# 4_digit_display.net
KiCad netlist of a schematic drawn in EAGLE
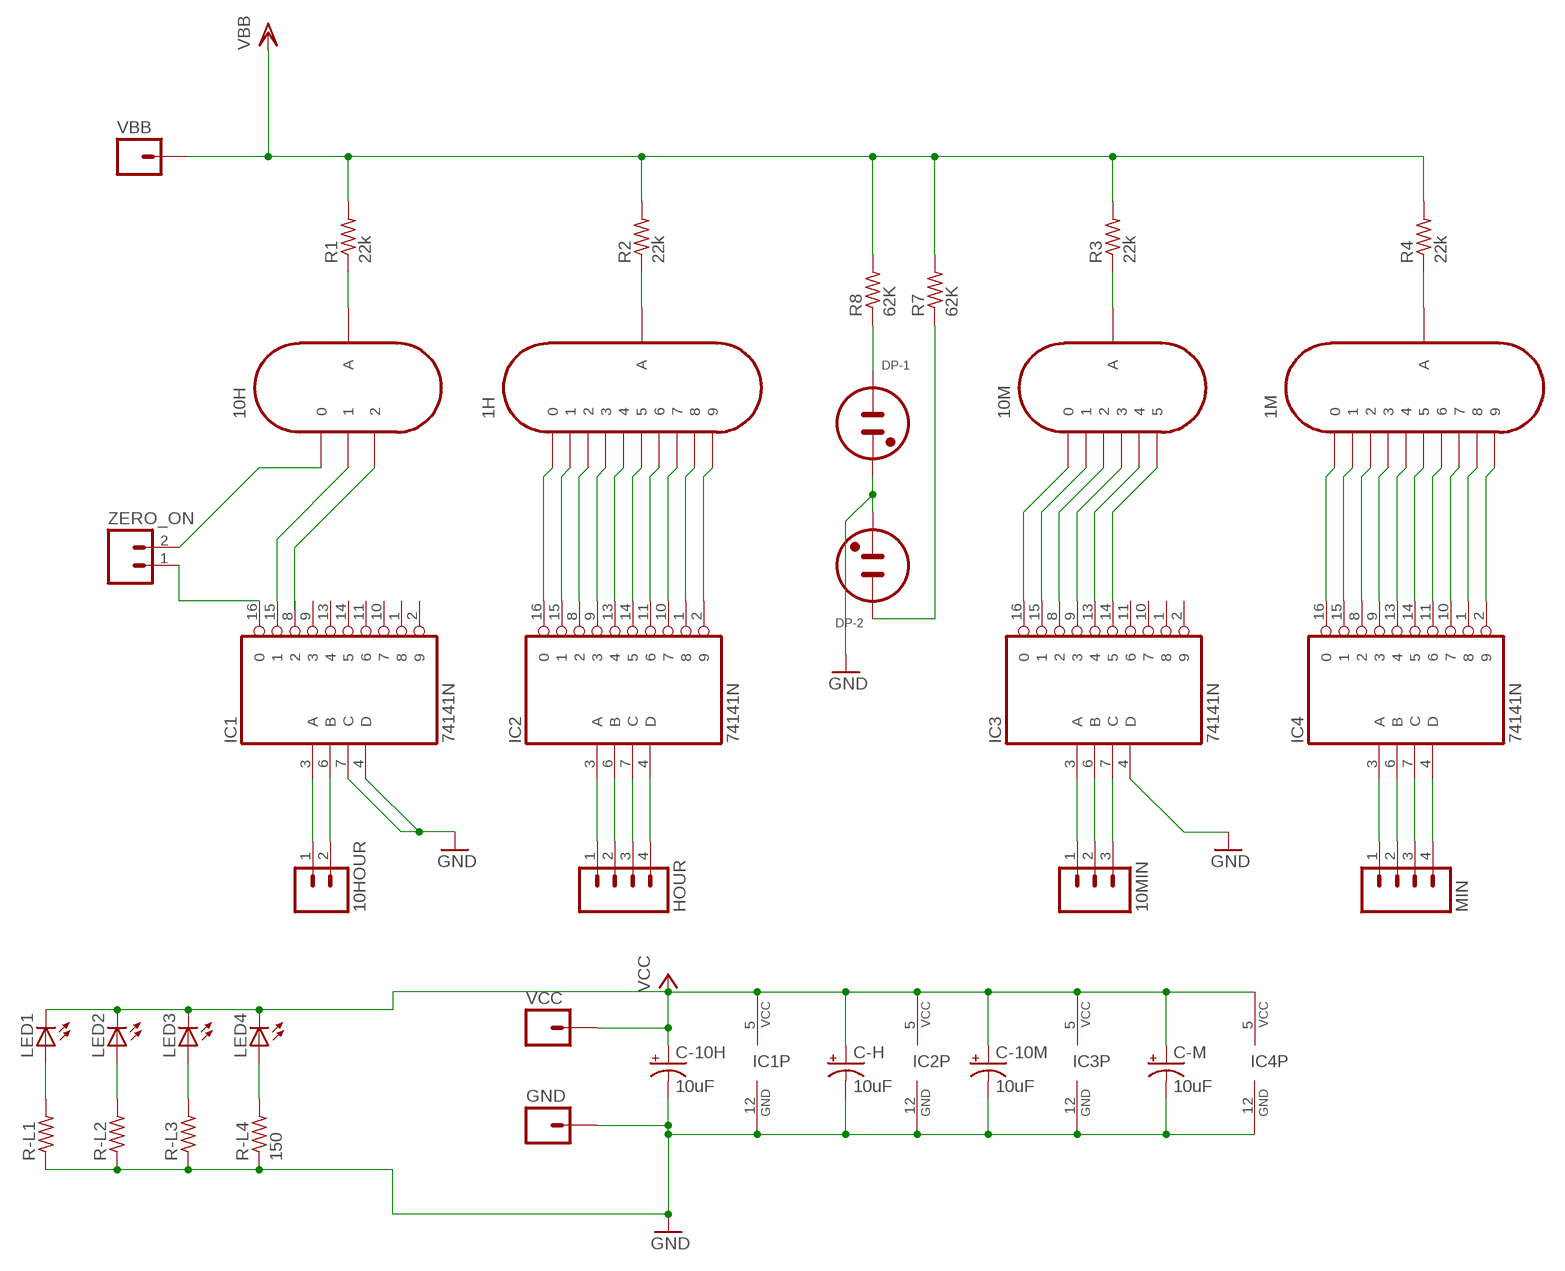
[diagram p0: schematic, sheet 1]

(export (version "E")
  (design (tool "Eeschema 10.0.6"))
  (components
    (comp (ref "1H")
      (value "IN-12A-NO_DP")
      (footprint "eagle-import:IN-12_NO-DP")
      (libsource (lib "eagle-import") (part "IN-12A-NO_DP"))
    )
    (comp (ref "1M")
      (value "IN-12A-NO_DP")
      (footprint "eagle-import:IN-12_NO-DP")
      (libsource (lib "eagle-import") (part "IN-12A-NO_DP"))
    )
    (comp (ref "10H")
      (value "IN-12_2DIGIT")
      (footprint "eagle-import:IN-12_2DIGIT")
      (libsource (lib "eagle-import") (part "IN-12_2DIGIT"))
    )
    (comp (ref "10HOUR")
      (value "M02PTH")
      (footprint "eagle-import:1X02")
      (libsource (lib "eagle-import") (part "M02PTH"))
    )
    (comp (ref "10M")
      (value "IN-12_6DIGIT")
      (footprint "eagle-import:IN-12_6DIGIT")
      (libsource (lib "eagle-import") (part "IN-12_6DIGIT"))
    )
    (comp (ref "10MIN")
      (value "M03PTH")
      (footprint "eagle-import:1X03")
      (libsource (lib "eagle-import") (part "M03PTH"))
    )
    (comp (ref "C-10H")
      (value "10uF")
      (footprint "eagle-import:B_3528-21R")
      (libsource (lib "eagle-import") (part "CAPACITOR_POLB/3528-21R"))
    )
    (comp (ref "C-10M")
      (value "10uF")
      (footprint "eagle-import:B_3528-21R")
      (libsource (lib "eagle-import") (part "CAPACITOR_POLB/3528-21R"))
    )
    (comp (ref "C-H")
      (value "10uF")
      (footprint "eagle-import:B_3528-21R")
      (libsource (lib "eagle-import") (part "CAPACITOR_POLB/3528-21R"))
    )
    (comp (ref "C-M")
      (value "10uF")
      (footprint "eagle-import:B_3528-21R")
      (libsource (lib "eagle-import") (part "CAPACITOR_POLB/3528-21R"))
    )
    (comp (ref "DP-1")
      (value "INS-1")
      (footprint "eagle-import:INS-1")
      (libsource (lib "eagle-import") (part "INS-1"))
    )
    (comp (ref "DP-2")
      (value "INS-1")
      (footprint "eagle-import:INS-1")
      (libsource (lib "eagle-import") (part "INS-1"))
    )
    (comp (ref "GND")
      (value "M01PTH")
      (footprint "eagle-import:1X01")
      (libsource (lib "eagle-import") (part "M01PTH"))
    )
    (comp (ref "HOUR")
      (value "M04PTH")
      (footprint "eagle-import:1X04")
      (libsource (lib "eagle-import") (part "M04PTH"))
    )
    (comp (ref "IC1")
      (value "74141N")
      (footprint "eagle-import:DIL16")
      (libsource (lib "eagle-import") (part "74141N"))
    )
    (comp (ref "IC2")
      (value "74141N")
      (footprint "eagle-import:DIL16")
      (libsource (lib "eagle-import") (part "74141N"))
    )
    (comp (ref "IC3")
      (value "74141N")
      (footprint "eagle-import:DIL16")
      (libsource (lib "eagle-import") (part "74141N"))
    )
    (comp (ref "IC4")
      (value "74141N")
      (footprint "eagle-import:DIL16")
      (libsource (lib "eagle-import") (part "74141N"))
    )
    (comp (ref "LED1")
      (value "LED1210")
      (footprint "eagle-import:LED1210")
      (libsource (lib "eagle-import") (part "LED1210"))
    )
    (comp (ref "LED2")
      (value "LED1210")
      (footprint "eagle-import:LED1210")
      (libsource (lib "eagle-import") (part "LED1210"))
    )
    (comp (ref "LED3")
      (value "LED1210")
      (footprint "eagle-import:LED1210")
      (libsource (lib "eagle-import") (part "LED1210"))
    )
    (comp (ref "LED4")
      (value "LED1210")
      (footprint "eagle-import:LED1210")
      (libsource (lib "eagle-import") (part "LED1210"))
    )
    (comp (ref "MIN")
      (value "M04PTH")
      (footprint "eagle-import:1X04")
      (libsource (lib "eagle-import") (part "M04PTH"))
    )
    (comp (ref "R-L1")
      (value "RESISTORR1206")
      (footprint "eagle-import:R1206")
      (libsource (lib "eagle-import") (part "RESISTORR1206"))
    )
    (comp (ref "R-L2")
      (value "RESISTORR1206")
      (footprint "eagle-import:R1206")
      (libsource (lib "eagle-import") (part "RESISTORR1206"))
    )
    (comp (ref "R-L3")
      (value "RESISTORR1206")
      (footprint "eagle-import:R1206")
      (libsource (lib "eagle-import") (part "RESISTORR1206"))
    )
    (comp (ref "R-L4")
      (value "150")
      (footprint "eagle-import:R1206")
      (libsource (lib "eagle-import") (part "RESISTORR1206"))
    )
    (comp (ref "R1")
      (value "22k")
      (footprint "eagle-import:0207_10")
      (libsource (lib "eagle-import") (part "RESISTOR0207/10"))
    )
    (comp (ref "R2")
      (value "22k")
      (footprint "eagle-import:0207_10")
      (libsource (lib "eagle-import") (part "RESISTOR0207/10"))
    )
    (comp (ref "R3")
      (value "22k")
      (footprint "eagle-import:0207_10")
      (libsource (lib "eagle-import") (part "RESISTOR0207/10"))
    )
    (comp (ref "R4")
      (value "22k")
      (footprint "eagle-import:0207_10")
      (libsource (lib "eagle-import") (part "RESISTOR0207/10"))
    )
    (comp (ref "R7")
      (value "62K")
      (footprint "eagle-import:0207_10")
      (libsource (lib "eagle-import") (part "RESISTOR0207/10"))
    )
    (comp (ref "R8")
      (value "62K")
      (footprint "eagle-import:0207_10")
      (libsource (lib "eagle-import") (part "RESISTOR0207/10"))
    )
    (comp (ref "VBB")
      (value "M01PTH")
      (footprint "eagle-import:1X01")
      (libsource (lib "eagle-import") (part "M01PTH"))
    )
    (comp (ref "VCC")
      (value "M01PTH")
      (footprint "eagle-import:1X01")
      (libsource (lib "eagle-import") (part "M01PTH"))
    )
    (comp (ref "ZERO_ON")
      (value "M02PTH")
      (footprint "eagle-import:1X02")
      (libsource (lib "eagle-import") (part "M02PTH"))
    )
  )
  (nets
    (net (code "1") (name "GND") (class "Default")
      (node (ref "C-10H") (pin "-") (pinfunction "-_-") (pintype "passive"))
      (node (ref "C-10M") (pin "-") (pinfunction "-_-") (pintype "passive"))
      (node (ref "C-H") (pin "-") (pinfunction "-_-") (pintype "passive"))
      (node (ref "C-M") (pin "-") (pinfunction "-_-") (pintype "passive"))
      (node (ref "DP-1") (pin "K") (pinfunction "K_K") (pintype "passive"))
      (node (ref "DP-2") (pin "K") (pinfunction "K_K") (pintype "passive"))
      (node (ref "GND") (pin "1") (pinfunction "1_1") (pintype "passive"))
      (node (ref "IC1") (pin "12") (pinfunction "GND_12") (pintype "power_in"))
      (node (ref "IC1") (pin "4") (pinfunction "D_4") (pintype "input"))
      (node (ref "IC1") (pin "7") (pinfunction "C_7") (pintype "input"))
      (node (ref "IC2") (pin "12") (pinfunction "GND_12") (pintype "power_in"))
      (node (ref "IC3") (pin "12") (pinfunction "GND_12") (pintype "power_in"))
      (node (ref "IC3") (pin "4") (pinfunction "D_4") (pintype "input"))
      (node (ref "IC4") (pin "12") (pinfunction "GND_12") (pintype "power_in"))
      (node (ref "R-L1") (pin "1") (pinfunction "1_1") (pintype "passive"))
      (node (ref "R-L2") (pin "1") (pinfunction "1_1") (pintype "passive"))
      (node (ref "R-L3") (pin "1") (pinfunction "1_1") (pintype "passive"))
      (node (ref "R-L4") (pin "1") (pinfunction "1_1") (pintype "passive"))
    )
    (net (code "2") (name "Net-(1H-PadA)") (class "Default")
      (node (ref "1H") (pin "A") (pinfunction "A_A") (pintype "bidirectional"))
      (node (ref "R2") (pin "1") (pinfunction "1_1") (pintype "passive"))
    )
    (net (code "3") (name "Net-(1M-PadA)") (class "Default")
      (node (ref "1M") (pin "A") (pinfunction "A_A") (pintype "bidirectional"))
      (node (ref "R4") (pin "1") (pinfunction "1_1") (pintype "passive"))
    )
    (net (code "4") (name "Net-(10H-Pad0)") (class "Default")
      (node (ref "10H") (pin "0") (pinfunction "0_0") (pintype "bidirectional"))
      (node (ref "ZERO_ON") (pin "2") (pinfunction "2_2") (pintype "passive"))
    )
    (net (code "5") (name "Net-(10H-PadA)") (class "Default")
      (node (ref "10H") (pin "A") (pinfunction "A_A") (pintype "bidirectional"))
      (node (ref "R1") (pin "1") (pinfunction "1_1") (pintype "passive"))
    )
    (net (code "6") (name "Net-(10M-PadA)") (class "Default")
      (node (ref "10M") (pin "A") (pinfunction "A_A") (pintype "bidirectional"))
      (node (ref "R3") (pin "1") (pinfunction "1_1") (pintype "passive"))
    )
    (net (code "7") (name "Net-(DP-1-PadA)") (class "Default")
      (node (ref "DP-1") (pin "A") (pinfunction "A_A") (pintype "passive"))
      (node (ref "R8") (pin "1") (pinfunction "1_1") (pintype "passive"))
    )
    (net (code "8") (name "Net-(DP-2-PadA)") (class "Default")
      (node (ref "DP-2") (pin "A") (pinfunction "A_A") (pintype "passive"))
      (node (ref "R7") (pin "1") (pinfunction "1_1") (pintype "passive"))
    )
    (net (code "9") (name "Net-(IC1A-0)") (class "Default")
      (node (ref "IC1") (pin "16") (pinfunction "0_16") (pintype "open_collector"))
      (node (ref "ZERO_ON") (pin "1") (pinfunction "1_1") (pintype "passive"))
    )
    (net (code "10") (name "Net-(IC1A-1)") (class "Default")
      (node (ref "10H") (pin "1") (pinfunction "1_1") (pintype "bidirectional"))
      (node (ref "IC1") (pin "15") (pinfunction "1_15") (pintype "open_collector"))
    )
    (net (code "11") (name "Net-(IC1A-A)") (class "Default")
      (node (ref "10HOUR") (pin "1") (pinfunction "1_1") (pintype "passive"))
      (node (ref "IC1") (pin "3") (pinfunction "A_3") (pintype "input"))
    )
    (net (code "12") (name "Net-(IC1A-B)") (class "Default")
      (node (ref "10HOUR") (pin "2") (pinfunction "2_2") (pintype "passive"))
      (node (ref "IC1") (pin "6") (pinfunction "B_6") (pintype "input"))
    )
    (net (code "13") (name "Net-(IC2A-0)") (class "Default")
      (node (ref "1H") (pin "0") (pinfunction "0_0") (pintype "bidirectional"))
      (node (ref "IC2") (pin "16") (pinfunction "0_16") (pintype "open_collector"))
    )
    (net (code "14") (name "Net-(IC2A-1)") (class "Default")
      (node (ref "1H") (pin "1") (pinfunction "1_1") (pintype "bidirectional"))
      (node (ref "IC2") (pin "15") (pinfunction "1_15") (pintype "open_collector"))
    )
    (net (code "15") (name "Net-(IC2A-2)") (class "Default")
      (node (ref "1H") (pin "2") (pinfunction "2_2") (pintype "bidirectional"))
      (node (ref "IC2") (pin "8") (pinfunction "2_8") (pintype "open_collector"))
    )
    (net (code "16") (name "Net-(IC2A-3)") (class "Default")
      (node (ref "1H") (pin "3") (pinfunction "3_3") (pintype "bidirectional"))
      (node (ref "IC2") (pin "9") (pinfunction "3_9") (pintype "open_collector"))
    )
    (net (code "17") (name "Net-(IC2A-4)") (class "Default")
      (node (ref "1H") (pin "4") (pinfunction "4_4") (pintype "bidirectional"))
      (node (ref "IC2") (pin "13") (pinfunction "4_13") (pintype "open_collector"))
    )
    (net (code "18") (name "Net-(IC2A-5)") (class "Default")
      (node (ref "1H") (pin "5") (pinfunction "5_5") (pintype "bidirectional"))
      (node (ref "IC2") (pin "14") (pinfunction "5_14") (pintype "open_collector"))
    )
    (net (code "19") (name "Net-(IC2A-6)") (class "Default")
      (node (ref "1H") (pin "6") (pinfunction "6_6") (pintype "bidirectional"))
      (node (ref "IC2") (pin "11") (pinfunction "6_11") (pintype "open_collector"))
    )
    (net (code "20") (name "Net-(IC2A-7)") (class "Default")
      (node (ref "1H") (pin "7") (pinfunction "7_7") (pintype "bidirectional"))
      (node (ref "IC2") (pin "10") (pinfunction "7_10") (pintype "open_collector"))
    )
    (net (code "21") (name "Net-(IC2A-8)") (class "Default")
      (node (ref "1H") (pin "8") (pinfunction "8_8") (pintype "bidirectional"))
      (node (ref "IC2") (pin "1") (pinfunction "8_1") (pintype "open_collector"))
    )
    (net (code "22") (name "Net-(IC2A-9)") (class "Default")
      (node (ref "1H") (pin "9") (pinfunction "9_9") (pintype "bidirectional"))
      (node (ref "IC2") (pin "2") (pinfunction "9_2") (pintype "open_collector"))
    )
    (net (code "23") (name "Net-(IC2A-A)") (class "Default")
      (node (ref "HOUR") (pin "1") (pinfunction "1_1") (pintype "passive"))
      (node (ref "IC2") (pin "3") (pinfunction "A_3") (pintype "input"))
    )
    (net (code "24") (name "Net-(IC2A-B)") (class "Default")
      (node (ref "HOUR") (pin "2") (pinfunction "2_2") (pintype "passive"))
      (node (ref "IC2") (pin "6") (pinfunction "B_6") (pintype "input"))
    )
    (net (code "25") (name "Net-(IC2A-C)") (class "Default")
      (node (ref "HOUR") (pin "3") (pinfunction "3_3") (pintype "passive"))
      (node (ref "IC2") (pin "7") (pinfunction "C_7") (pintype "input"))
    )
    (net (code "26") (name "Net-(IC2A-D)") (class "Default")
      (node (ref "HOUR") (pin "4") (pinfunction "4_4") (pintype "passive"))
      (node (ref "IC2") (pin "4") (pinfunction "D_4") (pintype "input"))
    )
    (net (code "27") (name "Net-(IC3A-0)") (class "Default")
      (node (ref "10M") (pin "0") (pinfunction "0_0") (pintype "bidirectional"))
      (node (ref "IC3") (pin "16") (pinfunction "0_16") (pintype "open_collector"))
    )
    (net (code "28") (name "Net-(IC3A-1)") (class "Default")
      (node (ref "10M") (pin "1") (pinfunction "1_1") (pintype "bidirectional"))
      (node (ref "IC3") (pin "15") (pinfunction "1_15") (pintype "open_collector"))
    )
    (net (code "29") (name "Net-(IC3A-2)") (class "Default")
      (node (ref "10M") (pin "2") (pinfunction "2_2") (pintype "bidirectional"))
      (node (ref "IC3") (pin "8") (pinfunction "2_8") (pintype "open_collector"))
    )
    (net (code "30") (name "Net-(IC3A-3)") (class "Default")
      (node (ref "10M") (pin "3") (pinfunction "3_3") (pintype "bidirectional"))
      (node (ref "IC3") (pin "9") (pinfunction "3_9") (pintype "open_collector"))
    )
    (net (code "31") (name "Net-(IC3A-4)") (class "Default")
      (node (ref "10M") (pin "4") (pinfunction "4_4") (pintype "bidirectional"))
      (node (ref "IC3") (pin "13") (pinfunction "4_13") (pintype "open_collector"))
    )
    (net (code "32") (name "Net-(IC3A-5)") (class "Default")
      (node (ref "10M") (pin "5") (pinfunction "5_5") (pintype "bidirectional"))
      (node (ref "IC3") (pin "14") (pinfunction "5_14") (pintype "open_collector"))
    )
    (net (code "33") (name "Net-(IC3A-A)") (class "Default")
      (node (ref "10MIN") (pin "1") (pinfunction "1_1") (pintype "passive"))
      (node (ref "IC3") (pin "3") (pinfunction "A_3") (pintype "input"))
    )
    (net (code "34") (name "Net-(IC3A-B)") (class "Default")
      (node (ref "10MIN") (pin "2") (pinfunction "2_2") (pintype "passive"))
      (node (ref "IC3") (pin "6") (pinfunction "B_6") (pintype "input"))
    )
    (net (code "35") (name "Net-(IC3A-C)") (class "Default")
      (node (ref "10MIN") (pin "3") (pinfunction "3_3") (pintype "passive"))
      (node (ref "IC3") (pin "7") (pinfunction "C_7") (pintype "input"))
    )
    (net (code "36") (name "Net-(IC4A-0)") (class "Default")
      (node (ref "1M") (pin "0") (pinfunction "0_0") (pintype "bidirectional"))
      (node (ref "IC4") (pin "16") (pinfunction "0_16") (pintype "open_collector"))
    )
    (net (code "37") (name "Net-(IC4A-1)") (class "Default")
      (node (ref "1M") (pin "1") (pinfunction "1_1") (pintype "bidirectional"))
      (node (ref "IC4") (pin "15") (pinfunction "1_15") (pintype "open_collector"))
    )
    (net (code "38") (name "Net-(IC4A-2)") (class "Default")
      (node (ref "1M") (pin "2") (pinfunction "2_2") (pintype "bidirectional"))
      (node (ref "IC4") (pin "8") (pinfunction "2_8") (pintype "open_collector"))
    )
    (net (code "39") (name "Net-(IC4A-3)") (class "Default")
      (node (ref "1M") (pin "3") (pinfunction "3_3") (pintype "bidirectional"))
      (node (ref "IC4") (pin "9") (pinfunction "3_9") (pintype "open_collector"))
    )
    (net (code "40") (name "Net-(IC4A-4)") (class "Default")
      (node (ref "1M") (pin "4") (pinfunction "4_4") (pintype "bidirectional"))
      (node (ref "IC4") (pin "13") (pinfunction "4_13") (pintype "open_collector"))
    )
    (net (code "41") (name "Net-(IC4A-5)") (class "Default")
      (node (ref "1M") (pin "5") (pinfunction "5_5") (pintype "bidirectional"))
      (node (ref "IC4") (pin "14") (pinfunction "5_14") (pintype "open_collector"))
    )
    (net (code "42") (name "Net-(IC4A-6)") (class "Default")
      (node (ref "1M") (pin "6") (pinfunction "6_6") (pintype "bidirectional"))
      (node (ref "IC4") (pin "11") (pinfunction "6_11") (pintype "open_collector"))
    )
    (net (code "43") (name "Net-(IC4A-7)") (class "Default")
      (node (ref "1M") (pin "7") (pinfunction "7_7") (pintype "bidirectional"))
      (node (ref "IC4") (pin "10") (pinfunction "7_10") (pintype "open_collector"))
    )
    (net (code "44") (name "Net-(IC4A-8)") (class "Default")
      (node (ref "1M") (pin "8") (pinfunction "8_8") (pintype "bidirectional"))
      (node (ref "IC4") (pin "1") (pinfunction "8_1") (pintype "open_collector"))
    )
    (net (code "45") (name "Net-(IC4A-9)") (class "Default")
      (node (ref "1M") (pin "9") (pinfunction "9_9") (pintype "bidirectional"))
      (node (ref "IC4") (pin "2") (pinfunction "9_2") (pintype "open_collector"))
    )
    (net (code "46") (name "Net-(IC4A-A)") (class "Default")
      (node (ref "IC4") (pin "3") (pinfunction "A_3") (pintype "input"))
      (node (ref "MIN") (pin "1") (pinfunction "1_1") (pintype "passive"))
    )
    (net (code "47") (name "Net-(IC4A-B)") (class "Default")
      (node (ref "IC4") (pin "6") (pinfunction "B_6") (pintype "input"))
      (node (ref "MIN") (pin "2") (pinfunction "2_2") (pintype "passive"))
    )
    (net (code "48") (name "Net-(IC4A-C)") (class "Default")
      (node (ref "IC4") (pin "7") (pinfunction "C_7") (pintype "input"))
      (node (ref "MIN") (pin "3") (pinfunction "3_3") (pintype "passive"))
    )
    (net (code "49") (name "Net-(IC4A-D)") (class "Default")
      (node (ref "IC4") (pin "4") (pinfunction "D_4") (pintype "input"))
      (node (ref "MIN") (pin "4") (pinfunction "4_4") (pintype "passive"))
    )
    (net (code "50") (name "Net-(LED1-PadA)") (class "Default")
      (node (ref "LED1") (pin "A") (pinfunction "A_A") (pintype "passive"))
      (node (ref "R-L1") (pin "2") (pinfunction "2_2") (pintype "passive"))
    )
    (net (code "51") (name "Net-(LED2-PadA)") (class "Default")
      (node (ref "LED2") (pin "A") (pinfunction "A_A") (pintype "passive"))
      (node (ref "R-L2") (pin "2") (pinfunction "2_2") (pintype "passive"))
    )
    (net (code "52") (name "Net-(LED3-PadA)") (class "Default")
      (node (ref "LED3") (pin "A") (pinfunction "A_A") (pintype "passive"))
      (node (ref "R-L3") (pin "2") (pinfunction "2_2") (pintype "passive"))
    )
    (net (code "53") (name "Net-(LED4-PadA)") (class "Default")
      (node (ref "LED4") (pin "A") (pinfunction "A_A") (pintype "passive"))
      (node (ref "R-L4") (pin "2") (pinfunction "2_2") (pintype "passive"))
    )
    (net (code "54") (name "VBB") (class "Default")
      (node (ref "R1") (pin "2") (pinfunction "2_2") (pintype "passive"))
      (node (ref "R2") (pin "2") (pinfunction "2_2") (pintype "passive"))
      (node (ref "R3") (pin "2") (pinfunction "2_2") (pintype "passive"))
      (node (ref "R4") (pin "2") (pinfunction "2_2") (pintype "passive"))
      (node (ref "R7") (pin "2") (pinfunction "2_2") (pintype "passive"))
      (node (ref "R8") (pin "2") (pinfunction "2_2") (pintype "passive"))
      (node (ref "VBB") (pin "1") (pinfunction "1_1") (pintype "passive"))
    )
    (net (code "55") (name "VCC") (class "Default")
      (node (ref "C-10H") (pin "+") (pinfunction "+_+") (pintype "passive"))
      (node (ref "C-10M") (pin "+") (pinfunction "+_+") (pintype "passive"))
      (node (ref "C-H") (pin "+") (pinfunction "+_+") (pintype "passive"))
      (node (ref "C-M") (pin "+") (pinfunction "+_+") (pintype "passive"))
      (node (ref "IC1") (pin "5") (pinfunction "VCC_5") (pintype "power_in"))
      (node (ref "IC2") (pin "5") (pinfunction "VCC_5") (pintype "power_in"))
      (node (ref "IC3") (pin "5") (pinfunction "VCC_5") (pintype "power_in"))
      (node (ref "IC4") (pin "5") (pinfunction "VCC_5") (pintype "power_in"))
      (node (ref "LED1") (pin "C") (pinfunction "C_C") (pintype "passive"))
      (node (ref "LED2") (pin "C") (pinfunction "C_C") (pintype "passive"))
      (node (ref "LED3") (pin "C") (pinfunction "C_C") (pintype "passive"))
      (node (ref "LED4") (pin "C") (pinfunction "C_C") (pintype "passive"))
      (node (ref "VCC") (pin "1") (pinfunction "1_1") (pintype "passive"))
    )
    (net (code "56") (name "unconnected-(10H-Pad2)") (class "Default")
      (node (ref "10H") (pin "2") (pinfunction "2_2") (pintype "bidirectional"))
    )
    (net (code "57") (name "unconnected-(IC1A-2-Pad8)") (class "Default")
      (node (ref "IC1") (pin "8") (pinfunction "2_8") (pintype "open_collector"))
    )
    (net (code "58") (name "unconnected-(IC1A-3-Pad9)") (class "Default")
      (node (ref "IC1") (pin "9") (pinfunction "3_9") (pintype "open_collector"))
    )
    (net (code "59") (name "unconnected-(IC1A-4-Pad13)") (class "Default")
      (node (ref "IC1") (pin "13") (pinfunction "4_13") (pintype "open_collector"))
    )
    (net (code "60") (name "unconnected-(IC1A-5-Pad14)") (class "Default")
      (node (ref "IC1") (pin "14") (pinfunction "5_14") (pintype "open_collector"))
    )
    (net (code "61") (name "unconnected-(IC1A-6-Pad11)") (class "Default")
      (node (ref "IC1") (pin "11") (pinfunction "6_11") (pintype "open_collector"))
    )
    (net (code "62") (name "unconnected-(IC1A-7-Pad10)") (class "Default")
      (node (ref "IC1") (pin "10") (pinfunction "7_10") (pintype "open_collector"))
    )
    (net (code "63") (name "unconnected-(IC1A-8-Pad1)") (class "Default")
      (node (ref "IC1") (pin "1") (pinfunction "8_1") (pintype "open_collector"))
    )
    (net (code "64") (name "unconnected-(IC1A-9-Pad2)") (class "Default")
      (node (ref "IC1") (pin "2") (pinfunction "9_2") (pintype "open_collector"))
    )
    (net (code "65") (name "unconnected-(IC3A-6-Pad11)") (class "Default")
      (node (ref "IC3") (pin "11") (pinfunction "6_11") (pintype "open_collector"))
    )
    (net (code "66") (name "unconnected-(IC3A-7-Pad10)") (class "Default")
      (node (ref "IC3") (pin "10") (pinfunction "7_10") (pintype "open_collector"))
    )
    (net (code "67") (name "unconnected-(IC3A-8-Pad1)") (class "Default")
      (node (ref "IC3") (pin "1") (pinfunction "8_1") (pintype "open_collector"))
    )
    (net (code "68") (name "unconnected-(IC3A-9-Pad2)") (class "Default")
      (node (ref "IC3") (pin "2") (pinfunction "9_2") (pintype "open_collector"))
    )
  )
)
